# ExosFeather.net
KiCad netlist of a schematic drawn in EAGLE
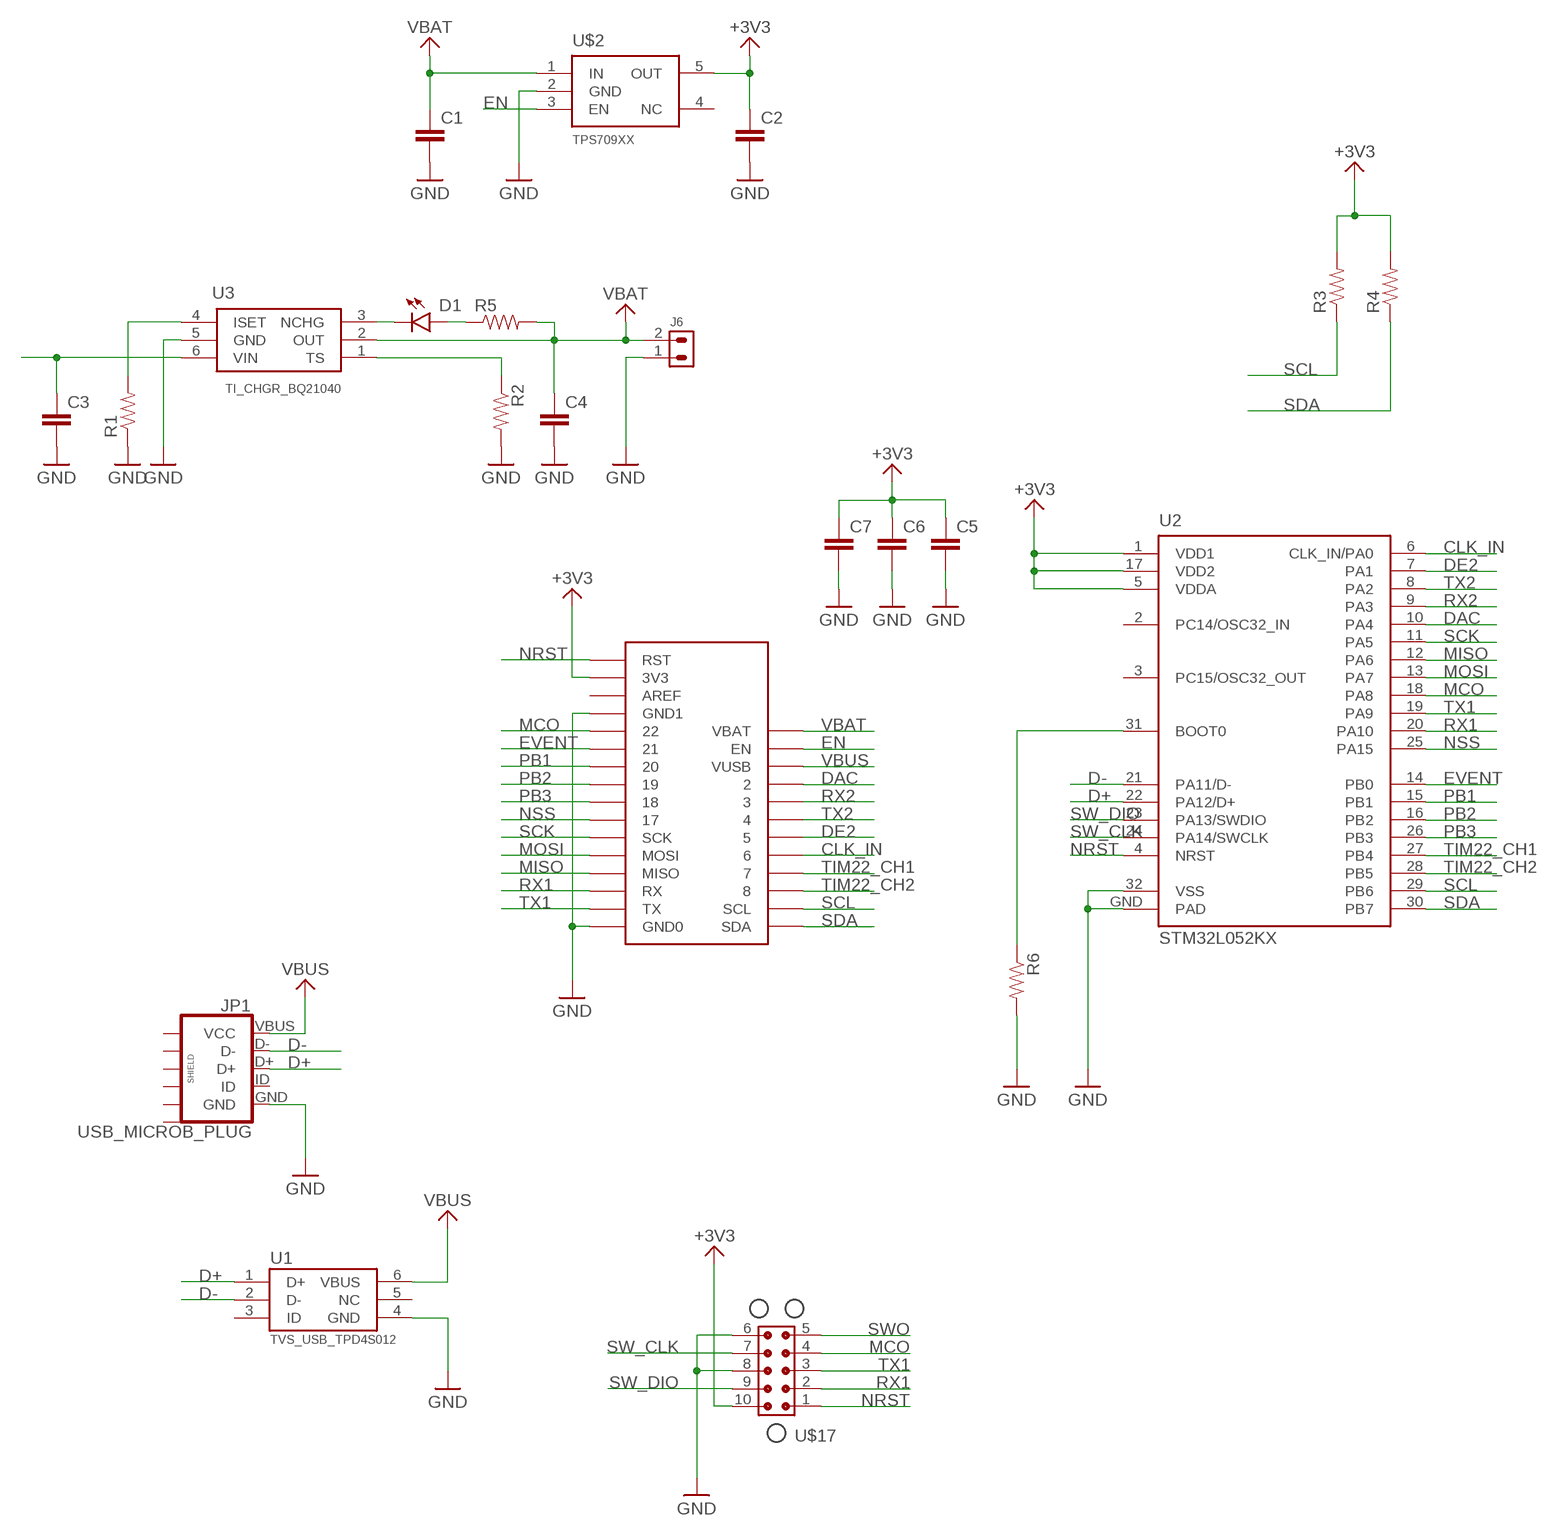
[diagram p0: schematic, sheet 1]

(export (version "E")
  (design (tool "Eeschema 10.0.6"))
  (components
    (comp (ref "C1")
      (value "0603_CAP")
      (footprint "eagle-import:0603")
      (libsource (lib "eagle-import") (part "0603_CAP"))
    )
    (comp (ref "C2")
      (value "0603_CAP")
      (footprint "eagle-import:0603")
      (libsource (lib "eagle-import") (part "0603_CAP"))
    )
    (comp (ref "C3")
      (value "0603_CAP")
      (footprint "eagle-import:0603")
      (libsource (lib "eagle-import") (part "0603_CAP"))
    )
    (comp (ref "C4")
      (value "0603_CAP")
      (footprint "eagle-import:0603")
      (libsource (lib "eagle-import") (part "0603_CAP"))
    )
    (comp (ref "C5")
      (value "0603_CAP")
      (footprint "eagle-import:0603")
      (libsource (lib "eagle-import") (part "0603_CAP"))
    )
    (comp (ref "C6")
      (value "0603_CAP")
      (footprint "eagle-import:0603")
      (libsource (lib "eagle-import") (part "0603_CAP"))
    )
    (comp (ref "C7")
      (value "0603_CAP")
      (footprint "eagle-import:0603")
      (libsource (lib "eagle-import") (part "0603_CAP"))
    )
    (comp (ref "D1")
      (value "0603_LED")
      (footprint "eagle-import:0603_LED")
      (libsource (lib "eagle-import") (part "0603_LED"))
    )
    (comp (ref "J6")
      (value "CONN_2X1_JST_PA")
      (footprint "eagle-import:CONN_2X1_JST_PA")
      (libsource (lib "eagle-import") (part "CONN_2X1_JST_PA"))
    )
    (comp (ref "JP1")
      (value "USB_MICROB_PLUG")
      (footprint "eagle-import:USB-MICROB")
      (libsource (lib "eagle-import") (part "USB_MICROB_PLUG"))
    )
    (comp (ref "R1")
      (value "0603_RES")
      (footprint "eagle-import:0603")
      (libsource (lib "eagle-import") (part "0603_RES"))
    )
    (comp (ref "R2")
      (value "0603_RES")
      (footprint "eagle-import:0603")
      (libsource (lib "eagle-import") (part "0603_RES"))
    )
    (comp (ref "R3")
      (value "0603_RES")
      (footprint "eagle-import:0603")
      (libsource (lib "eagle-import") (part "0603_RES"))
    )
    (comp (ref "R4")
      (value "0603_RES")
      (footprint "eagle-import:0603")
      (libsource (lib "eagle-import") (part "0603_RES"))
    )
    (comp (ref "R5")
      (value "0603_RES")
      (footprint "eagle-import:0603")
      (libsource (lib "eagle-import") (part "0603_RES"))
    )
    (comp (ref "R6")
      (value "0603_RES")
      (footprint "eagle-import:0603")
      (libsource (lib "eagle-import") (part "0603_RES"))
    )
    (comp (ref "U$1")
      (value "FEATHER_PINOUT_FULL")
      (footprint "eagle-import:FEATHER_PINOUT_FULL")
      (libsource (lib "eagle-import") (part "FEATHER_PINOUT_FULL"))
    )
    (comp (ref "U$2")
      (value "TPS709XX")
      (footprint "eagle-import:SOT23-5")
      (libsource (lib "eagle-import") (part "TPS709XX"))
    )
    (comp (ref "U$17")
      (value "TC_2050_IDC_TOP")
      (footprint "eagle-import:TC_2050_IC_TOP")
      (libsource (lib "eagle-import") (part "TC_2050_IDC_TOP"))
    )
    (comp (ref "U1")
      (value "TVS_USB_TPD4S012")
      (footprint "eagle-import:USB_TVS_TPD4S012")
      (libsource (lib "eagle-import") (part "TVS_USB_TPD4S012"))
    )
    (comp (ref "U2")
      (value "STM32L052KX")
      (footprint "eagle-import:STM32_QFN_32_5X5")
      (libsource (lib "eagle-import") (part "STM32L052KX"))
    )
    (comp (ref "U3")
      (value "TI_CHGR_BQ21040")
      (footprint "eagle-import:SOT-23-6_TI")
      (libsource (lib "eagle-import") (part "TI_CHGR_BQ21040"))
    )
  )
  (nets
    (net (code "1") (name "/CLK_IN") (class "Default")
      (node (ref "U$1") (pin "P$8") (pinfunction "6_P$8") (pintype "bidirectional"))
      (node (ref "U2") (pin "6") (pinfunction "CLK_IN/PA0_6") (pintype "bidirectional"))
    )
    (net (code "2") (name "/D+") (class "Default")
      (node (ref "JP1") (pin "D+") (pinfunction "D+_D+") (pintype "bidirectional"))
      (node (ref "U1") (pin "1") (pinfunction "D+_1") (pintype "bidirectional"))
      (node (ref "U2") (pin "22") (pinfunction "PA12/D+_22") (pintype "bidirectional"))
    )
    (net (code "3") (name "/D-") (class "Default")
      (node (ref "JP1") (pin "D-") (pinfunction "D-_D-") (pintype "bidirectional"))
      (node (ref "U1") (pin "2") (pinfunction "D-_2") (pintype "bidirectional"))
      (node (ref "U2") (pin "21") (pinfunction "PA11/D-_21") (pintype "bidirectional"))
    )
    (net (code "4") (name "/DAC") (class "Default")
      (node (ref "U$1") (pin "P$4") (pinfunction "2_P$4") (pintype "bidirectional"))
      (node (ref "U2") (pin "10") (pinfunction "PA4_10") (pintype "bidirectional"))
    )
    (net (code "5") (name "/DE2") (class "Default")
      (node (ref "U$1") (pin "P$7") (pinfunction "5_P$7") (pintype "bidirectional"))
      (node (ref "U2") (pin "7") (pinfunction "PA1_7") (pintype "bidirectional"))
    )
    (net (code "6") (name "/EN") (class "Default")
      (node (ref "U$1") (pin "P$2") (pinfunction "EN_P$2") (pintype "bidirectional"))
      (node (ref "U$2") (pin "3") (pinfunction "EN_3") (pintype "bidirectional"))
    )
    (net (code "7") (name "/EVENT") (class "Default")
      (node (ref "U$1") (pin "P$23") (pinfunction "21_P$23") (pintype "bidirectional"))
      (node (ref "U2") (pin "14") (pinfunction "PB0_14") (pintype "bidirectional"))
    )
    (net (code "8") (name "/MCO") (class "Default")
      (node (ref "U$1") (pin "P$24") (pinfunction "22_P$24") (pintype "bidirectional"))
      (node (ref "U$17") (pin "4") (pinfunction "4_4") (pintype "bidirectional"))
      (node (ref "U2") (pin "18") (pinfunction "PA8_18") (pintype "bidirectional"))
    )
    (net (code "9") (name "/MISO") (class "Default")
      (node (ref "U$1") (pin "P$16") (pinfunction "MISO_P$16") (pintype "bidirectional"))
      (node (ref "U2") (pin "12") (pinfunction "PA6_12") (pintype "bidirectional"))
    )
    (net (code "10") (name "/MOSI") (class "Default")
      (node (ref "U$1") (pin "P$17") (pinfunction "MOSI_P$17") (pintype "bidirectional"))
      (node (ref "U2") (pin "13") (pinfunction "PA7_13") (pintype "bidirectional"))
    )
    (net (code "11") (name "/NRST") (class "Default")
      (node (ref "U$1") (pin "P$28") (pinfunction "RST_P$28") (pintype "bidirectional"))
      (node (ref "U$17") (pin "1") (pinfunction "1_1") (pintype "bidirectional"))
      (node (ref "U2") (pin "4") (pinfunction "NRST_4") (pintype "bidirectional"))
    )
    (net (code "12") (name "/NSS") (class "Default")
      (node (ref "U$1") (pin "P$19") (pinfunction "17_P$19") (pintype "bidirectional"))
      (node (ref "U2") (pin "25") (pinfunction "PA15_25") (pintype "bidirectional"))
    )
    (net (code "13") (name "/PB1") (class "Default")
      (node (ref "U$1") (pin "P$22") (pinfunction "20_P$22") (pintype "bidirectional"))
      (node (ref "U2") (pin "15") (pinfunction "PB1_15") (pintype "bidirectional"))
    )
    (net (code "14") (name "/PB2") (class "Default")
      (node (ref "U$1") (pin "P$21") (pinfunction "19_P$21") (pintype "bidirectional"))
      (node (ref "U2") (pin "16") (pinfunction "PB2_16") (pintype "bidirectional"))
    )
    (net (code "15") (name "/PB3") (class "Default")
      (node (ref "U$1") (pin "P$20") (pinfunction "18_P$20") (pintype "bidirectional"))
      (node (ref "U2") (pin "26") (pinfunction "PB3_26") (pintype "bidirectional"))
    )
    (net (code "16") (name "/RX1") (class "Default")
      (node (ref "U$1") (pin "P$15") (pinfunction "RX_P$15") (pintype "bidirectional"))
      (node (ref "U$17") (pin "2") (pinfunction "2_2") (pintype "bidirectional"))
      (node (ref "U2") (pin "20") (pinfunction "PA10_20") (pintype "bidirectional"))
    )
    (net (code "17") (name "/RX2") (class "Default")
      (node (ref "U$1") (pin "P$5") (pinfunction "3_P$5") (pintype "bidirectional"))
      (node (ref "U2") (pin "9") (pinfunction "PA3_9") (pintype "bidirectional"))
    )
    (net (code "18") (name "/SCK") (class "Default")
      (node (ref "U$1") (pin "P$18") (pinfunction "SCK_P$18") (pintype "bidirectional"))
      (node (ref "U2") (pin "11") (pinfunction "PA5_11") (pintype "bidirectional"))
    )
    (net (code "19") (name "/SCL") (class "Default")
      (node (ref "R3") (pin "P$1") (pinfunction "1_P$1") (pintype "passive"))
      (node (ref "U$1") (pin "P$11") (pinfunction "SCL_P$11") (pintype "bidirectional"))
      (node (ref "U2") (pin "29") (pinfunction "PB6_29") (pintype "bidirectional"))
    )
    (net (code "20") (name "/SDA") (class "Default")
      (node (ref "R4") (pin "P$1") (pinfunction "1_P$1") (pintype "passive"))
      (node (ref "U$1") (pin "P$12") (pinfunction "SDA_P$12") (pintype "bidirectional"))
      (node (ref "U2") (pin "30") (pinfunction "PB7_30") (pintype "bidirectional"))
    )
    (net (code "21") (name "/SWO") (class "Default")
      (node (ref "U$17") (pin "5") (pinfunction "5_5") (pintype "bidirectional"))
    )
    (net (code "22") (name "/SW_CLK") (class "Default")
      (node (ref "U$17") (pin "7") (pinfunction "7_7") (pintype "bidirectional"))
      (node (ref "U2") (pin "24") (pinfunction "PA14/SWCLK_24") (pintype "bidirectional"))
    )
    (net (code "23") (name "/SW_DIO") (class "Default")
      (node (ref "U$17") (pin "9") (pinfunction "9_9") (pintype "bidirectional"))
      (node (ref "U2") (pin "23") (pinfunction "PA13/SWDIO_23") (pintype "bidirectional"))
    )
    (net (code "24") (name "/TIM22_CH1") (class "Default")
      (node (ref "U$1") (pin "P$9") (pinfunction "7_P$9") (pintype "bidirectional"))
      (node (ref "U2") (pin "27") (pinfunction "PB4_27") (pintype "bidirectional"))
    )
    (net (code "25") (name "/TIM22_CH2") (class "Default")
      (node (ref "U$1") (pin "P$10") (pinfunction "8_P$10") (pintype "bidirectional"))
      (node (ref "U2") (pin "28") (pinfunction "PB5_28") (pintype "bidirectional"))
    )
    (net (code "26") (name "/TX1") (class "Default")
      (node (ref "U$1") (pin "P$14") (pinfunction "TX_P$14") (pintype "bidirectional"))
      (node (ref "U$17") (pin "3") (pinfunction "3_3") (pintype "bidirectional"))
      (node (ref "U2") (pin "19") (pinfunction "PA9_19") (pintype "bidirectional"))
    )
    (net (code "27") (name "/TX2") (class "Default")
      (node (ref "U$1") (pin "P$6") (pinfunction "4_P$6") (pintype "bidirectional"))
      (node (ref "U2") (pin "8") (pinfunction "PA2_8") (pintype "bidirectional"))
    )
    (net (code "28") (name "GND") (class "Default")
      (node (ref "C1") (pin "P$2") (pinfunction "2_P$2") (pintype "passive"))
      (node (ref "C2") (pin "P$2") (pinfunction "2_P$2") (pintype "passive"))
      (node (ref "C3") (pin "P$2") (pinfunction "2_P$2") (pintype "passive"))
      (node (ref "C4") (pin "P$2") (pinfunction "2_P$2") (pintype "passive"))
      (node (ref "C5") (pin "P$2") (pinfunction "2_P$2") (pintype "passive"))
      (node (ref "C6") (pin "P$2") (pinfunction "2_P$2") (pintype "passive"))
      (node (ref "C7") (pin "P$2") (pinfunction "2_P$2") (pintype "passive"))
      (node (ref "J6") (pin "1") (pinfunction "1_1") (pintype "bidirectional"))
      (node (ref "JP1") (pin "GND") (pinfunction "GND_GND") (pintype "bidirectional"))
      (node (ref "R1") (pin "P$1") (pinfunction "1_P$1") (pintype "passive"))
      (node (ref "R2") (pin "P$2") (pinfunction "2_P$2") (pintype "passive"))
      (node (ref "R6") (pin "P$2") (pinfunction "2_P$2") (pintype "passive"))
      (node (ref "U$1") (pin "P$13") (pinfunction "GND0_P$13") (pintype "bidirectional"))
      (node (ref "U$1") (pin "P$25") (pinfunction "GND1_P$25") (pintype "bidirectional"))
      (node (ref "U$17") (pin "6") (pinfunction "6_6") (pintype "bidirectional"))
      (node (ref "U$17") (pin "8") (pinfunction "8_8") (pintype "bidirectional"))
      (node (ref "U$2") (pin "2") (pinfunction "GND_2") (pintype "bidirectional"))
      (node (ref "U1") (pin "4") (pinfunction "GND_4") (pintype "bidirectional"))
      (node (ref "U2") (pin "32") (pinfunction "VSS_32") (pintype "bidirectional"))
      (node (ref "U2") (pin "GND") (pinfunction "PAD_GND") (pintype "bidirectional"))
      (node (ref "U3") (pin "5") (pinfunction "GND_5") (pintype "bidirectional"))
    )
    (net (code "29") (name "Net-(D1-A)") (class "Default")
      (node (ref "D1") (pin "P$1") (pinfunction "A_P$1") (pintype "passive"))
      (node (ref "R5") (pin "P$1") (pinfunction "1_P$1") (pintype "passive"))
    )
    (net (code "30") (name "Net-(D1-C)") (class "Default")
      (node (ref "D1") (pin "P$2") (pinfunction "C_P$2") (pintype "passive"))
      (node (ref "U3") (pin "3") (pinfunction "NCHG_3") (pintype "bidirectional"))
    )
    (net (code "31") (name "Net-(R1-2)") (class "Default")
      (node (ref "R1") (pin "P$2") (pinfunction "2_P$2") (pintype "passive"))
      (node (ref "U3") (pin "4") (pinfunction "ISET_4") (pintype "bidirectional"))
    )
    (net (code "32") (name "Net-(R2-1)") (class "Default")
      (node (ref "R2") (pin "P$1") (pinfunction "1_P$1") (pintype "passive"))
      (node (ref "U3") (pin "1") (pinfunction "TS_1") (pintype "bidirectional"))
    )
    (net (code "33") (name "Net-(R6-1)") (class "Default")
      (node (ref "R6") (pin "P$1") (pinfunction "1_P$1") (pintype "passive"))
      (node (ref "U2") (pin "31") (pinfunction "BOOT0_31") (pintype "bidirectional"))
    )
    (net (code "34") (name "SUP_+3V3") (class "Default")
      (node (ref "C2") (pin "P$1") (pinfunction "1_P$1") (pintype "passive"))
      (node (ref "C5") (pin "P$1") (pinfunction "1_P$1") (pintype "passive"))
      (node (ref "C6") (pin "P$1") (pinfunction "1_P$1") (pintype "passive"))
      (node (ref "C7") (pin "P$1") (pinfunction "1_P$1") (pintype "passive"))
      (node (ref "R3") (pin "P$2") (pinfunction "2_P$2") (pintype "passive"))
      (node (ref "R4") (pin "P$2") (pinfunction "2_P$2") (pintype "passive"))
      (node (ref "U$1") (pin "P$27") (pinfunction "3V3_P$27") (pintype "bidirectional"))
      (node (ref "U$17") (pin "10") (pinfunction "10_10") (pintype "bidirectional"))
      (node (ref "U$2") (pin "5") (pinfunction "OUT_5") (pintype "bidirectional"))
      (node (ref "U2") (pin "1") (pinfunction "VDD1_1") (pintype "bidirectional"))
      (node (ref "U2") (pin "17") (pinfunction "VDD2_17") (pintype "bidirectional"))
      (node (ref "U2") (pin "5") (pinfunction "VDDA_5") (pintype "bidirectional"))
    )
    (net (code "35") (name "SUP_VBAT") (class "Default")
      (node (ref "C1") (pin "P$1") (pinfunction "1_P$1") (pintype "passive"))
      (node (ref "C4") (pin "P$1") (pinfunction "1_P$1") (pintype "passive"))
      (node (ref "J6") (pin "2") (pinfunction "2_2") (pintype "bidirectional"))
      (node (ref "R5") (pin "P$2") (pinfunction "2_P$2") (pintype "passive"))
      (node (ref "U$1") (pin "P$1") (pinfunction "VBAT_P$1") (pintype "bidirectional"))
      (node (ref "U$2") (pin "1") (pinfunction "IN_1") (pintype "bidirectional"))
      (node (ref "U3") (pin "2") (pinfunction "OUT_2") (pintype "bidirectional"))
    )
    (net (code "36") (name "SUP_VBUS") (class "Default")
      (node (ref "C3") (pin "P$1") (pinfunction "1_P$1") (pintype "passive"))
      (node (ref "JP1") (pin "VBUS") (pinfunction "VCC_VBUS") (pintype "bidirectional"))
      (node (ref "U$1") (pin "P$3") (pinfunction "VUSB_P$3") (pintype "bidirectional"))
      (node (ref "U1") (pin "6") (pinfunction "VBUS_6") (pintype "bidirectional"))
      (node (ref "U3") (pin "6") (pinfunction "VIN_6") (pintype "bidirectional"))
    )
    (net (code "37") (name "unconnected-(JP1-PadID)") (class "Default")
      (node (ref "JP1") (pin "ID") (pinfunction "ID_ID") (pintype "bidirectional"))
    )
    (net (code "38") (name "unconnected-(JP1-SHIELD-PadMT1)") (class "Default")
      (node (ref "JP1") (pin "MT1") (pinfunction "SHIELD_MT1") (pintype "bidirectional"))
    )
    (net (code "39") (name "unconnected-(JP1-SHIELD1-PadMT2)") (class "Default")
      (node (ref "JP1") (pin "MT2") (pinfunction "SHIELD1_MT2") (pintype "bidirectional"))
    )
    (net (code "40") (name "unconnected-(JP1-SHIELD2-PadP$1)") (class "Default")
      (node (ref "JP1") (pin "P$1") (pinfunction "SHIELD2_P$1") (pintype "bidirectional"))
    )
    (net (code "41") (name "unconnected-(JP1-SHIELD3-PadP$2)") (class "Default")
      (node (ref "JP1") (pin "P$2") (pinfunction "SHIELD3_P$2") (pintype "bidirectional"))
    )
    (net (code "42") (name "unconnected-(JP1-SHIELD4-PadP$3)") (class "Default")
      (node (ref "JP1") (pin "P$3") (pinfunction "SHIELD4_P$3") (pintype "bidirectional"))
    )
    (net (code "43") (name "unconnected-(JP1-SHIELD5-PadP$4)") (class "Default")
      (node (ref "JP1") (pin "P$4") (pinfunction "SHIELD5_P$4") (pintype "bidirectional"))
    )
    (net (code "44") (name "unconnected-(U$1-AREF-PadP$26)") (class "Default")
      (node (ref "U$1") (pin "P$26") (pinfunction "AREF_P$26") (pintype "bidirectional"))
    )
    (net (code "45") (name "unconnected-(U$2-NC-Pad4)") (class "Default")
      (node (ref "U$2") (pin "4") (pinfunction "NC_4") (pintype "bidirectional"))
    )
    (net (code "46") (name "unconnected-(U1-ID-Pad3)") (class "Default")
      (node (ref "U1") (pin "3") (pinfunction "ID_3") (pintype "bidirectional"))
    )
    (net (code "47") (name "unconnected-(U1-NC-Pad5)") (class "Default")
      (node (ref "U1") (pin "5") (pinfunction "NC_5") (pintype "bidirectional"))
    )
    (net (code "48") (name "unconnected-(U2-PC14{slash}OSC32_IN-Pad2)") (class "Default")
      (node (ref "U2") (pin "2") (pinfunction "PC14/OSC32_IN_2") (pintype "bidirectional"))
    )
    (net (code "49") (name "unconnected-(U2-PC15{slash}OSC32_OUT-Pad3)") (class "Default")
      (node (ref "U2") (pin "3") (pinfunction "PC15/OSC32_OUT_3") (pintype "bidirectional"))
    )
  )
)
